# esp32_hr_module.net
KiCad netlist of a schematic drawn in EAGLE
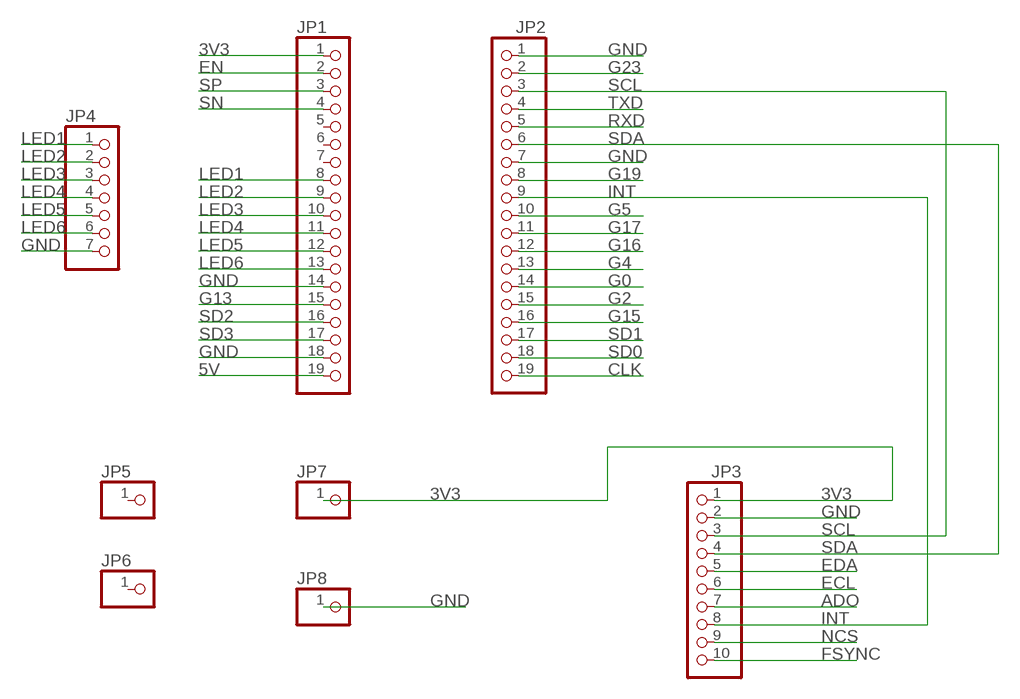
[diagram p0: schematic, sheet 1]

(export (version "E")
  (design (tool "Eeschema 10.0.6"))
  (components
    (comp (ref "JP1")
      (value "PINHD-1X19")
      (footprint "eagle-import:1X19")
      (libsource (lib "eagle-import") (part "PINHD-1X19"))
    )
    (comp (ref "JP2")
      (value "PINHD-1X19")
      (footprint "eagle-import:1X19")
      (libsource (lib "eagle-import") (part "PINHD-1X19"))
    )
    (comp (ref "JP3")
      (value "PINHD-1X10")
      (footprint "eagle-import:1X10")
      (libsource (lib "eagle-import") (part "PINHD-1X10"))
    )
    (comp (ref "JP4")
      (value "PINHD-1X7")
      (footprint "eagle-import:1X07")
      (libsource (lib "eagle-import") (part "PINHD-1X7"))
    )
    (comp (ref "JP5")
      (value "PINHD-1X1")
      (footprint "eagle-import:1X01")
      (libsource (lib "eagle-import") (part "PINHD-1X1"))
    )
    (comp (ref "JP6")
      (value "PINHD-1X1")
      (footprint "eagle-import:1X01")
      (libsource (lib "eagle-import") (part "PINHD-1X1"))
    )
    (comp (ref "JP7")
      (value "PINHD-1X1")
      (footprint "eagle-import:1X01")
      (libsource (lib "eagle-import") (part "PINHD-1X1"))
    )
    (comp (ref "JP8")
      (value "PINHD-1X1")
      (footprint "eagle-import:1X01")
      (libsource (lib "eagle-import") (part "PINHD-1X1"))
    )
  )
  (nets
    (net (code "1") (name "/3V3") (class "Default")
      (node (ref "JP1") (pin "1") (pinfunction "1_1") (pintype "passive"))
      (node (ref "JP3") (pin "1") (pinfunction "1_1") (pintype "passive"))
      (node (ref "JP7") (pin "1") (pinfunction "1_1") (pintype "passive"))
    )
    (net (code "2") (name "/5V") (class "Default")
      (node (ref "JP1") (pin "19") (pinfunction "19_19") (pintype "passive"))
    )
    (net (code "3") (name "/ADO") (class "Default")
      (node (ref "JP3") (pin "7") (pinfunction "7_7") (pintype "passive"))
    )
    (net (code "4") (name "/CLK") (class "Default")
      (node (ref "JP2") (pin "19") (pinfunction "19_19") (pintype "passive"))
    )
    (net (code "5") (name "/ECL") (class "Default")
      (node (ref "JP3") (pin "6") (pinfunction "6_6") (pintype "passive"))
    )
    (net (code "6") (name "/EDA") (class "Default")
      (node (ref "JP3") (pin "5") (pinfunction "5_5") (pintype "passive"))
    )
    (net (code "7") (name "/EN") (class "Default")
      (node (ref "JP1") (pin "2") (pinfunction "2_2") (pintype "passive"))
    )
    (net (code "8") (name "/FSYNC") (class "Default")
      (node (ref "JP3") (pin "10") (pinfunction "10_10") (pintype "passive"))
    )
    (net (code "9") (name "/G0") (class "Default")
      (node (ref "JP2") (pin "14") (pinfunction "14_14") (pintype "passive"))
    )
    (net (code "10") (name "/G2") (class "Default")
      (node (ref "JP2") (pin "15") (pinfunction "15_15") (pintype "passive"))
    )
    (net (code "11") (name "/G4") (class "Default")
      (node (ref "JP2") (pin "13") (pinfunction "13_13") (pintype "passive"))
    )
    (net (code "12") (name "/G5") (class "Default")
      (node (ref "JP2") (pin "10") (pinfunction "10_10") (pintype "passive"))
    )
    (net (code "13") (name "/G13") (class "Default")
      (node (ref "JP1") (pin "15") (pinfunction "15_15") (pintype "passive"))
    )
    (net (code "14") (name "/G15") (class "Default")
      (node (ref "JP2") (pin "16") (pinfunction "16_16") (pintype "passive"))
    )
    (net (code "15") (name "/G16") (class "Default")
      (node (ref "JP2") (pin "12") (pinfunction "12_12") (pintype "passive"))
    )
    (net (code "16") (name "/G17") (class "Default")
      (node (ref "JP2") (pin "11") (pinfunction "11_11") (pintype "passive"))
    )
    (net (code "17") (name "/G19") (class "Default")
      (node (ref "JP2") (pin "8") (pinfunction "8_8") (pintype "passive"))
    )
    (net (code "18") (name "/G23") (class "Default")
      (node (ref "JP2") (pin "2") (pinfunction "2_2") (pintype "passive"))
    )
    (net (code "19") (name "/GND") (class "Default")
      (node (ref "JP1") (pin "14") (pinfunction "14_14") (pintype "passive"))
      (node (ref "JP1") (pin "18") (pinfunction "18_18") (pintype "passive"))
      (node (ref "JP2") (pin "1") (pinfunction "1_1") (pintype "passive"))
      (node (ref "JP2") (pin "7") (pinfunction "7_7") (pintype "passive"))
      (node (ref "JP3") (pin "2") (pinfunction "2_2") (pintype "passive"))
      (node (ref "JP4") (pin "7") (pinfunction "7_7") (pintype "passive"))
      (node (ref "JP8") (pin "1") (pinfunction "1_1") (pintype "passive"))
    )
    (net (code "20") (name "/INT") (class "Default")
      (node (ref "JP2") (pin "9") (pinfunction "9_9") (pintype "passive"))
      (node (ref "JP3") (pin "8") (pinfunction "8_8") (pintype "passive"))
    )
    (net (code "21") (name "/LED1") (class "Default")
      (node (ref "JP1") (pin "8") (pinfunction "8_8") (pintype "passive"))
      (node (ref "JP4") (pin "1") (pinfunction "1_1") (pintype "passive"))
    )
    (net (code "22") (name "/LED2") (class "Default")
      (node (ref "JP1") (pin "9") (pinfunction "9_9") (pintype "passive"))
      (node (ref "JP4") (pin "2") (pinfunction "2_2") (pintype "passive"))
    )
    (net (code "23") (name "/LED3") (class "Default")
      (node (ref "JP1") (pin "10") (pinfunction "10_10") (pintype "passive"))
      (node (ref "JP4") (pin "3") (pinfunction "3_3") (pintype "passive"))
    )
    (net (code "24") (name "/LED4") (class "Default")
      (node (ref "JP1") (pin "11") (pinfunction "11_11") (pintype "passive"))
      (node (ref "JP4") (pin "4") (pinfunction "4_4") (pintype "passive"))
    )
    (net (code "25") (name "/LED5") (class "Default")
      (node (ref "JP1") (pin "12") (pinfunction "12_12") (pintype "passive"))
      (node (ref "JP4") (pin "5") (pinfunction "5_5") (pintype "passive"))
    )
    (net (code "26") (name "/LED6") (class "Default")
      (node (ref "JP1") (pin "13") (pinfunction "13_13") (pintype "passive"))
      (node (ref "JP4") (pin "6") (pinfunction "6_6") (pintype "passive"))
    )
    (net (code "27") (name "/NCS") (class "Default")
      (node (ref "JP3") (pin "9") (pinfunction "9_9") (pintype "passive"))
    )
    (net (code "28") (name "/RXD") (class "Default")
      (node (ref "JP2") (pin "5") (pinfunction "5_5") (pintype "passive"))
    )
    (net (code "29") (name "/SCL") (class "Default")
      (node (ref "JP2") (pin "3") (pinfunction "3_3") (pintype "passive"))
      (node (ref "JP3") (pin "3") (pinfunction "3_3") (pintype "passive"))
    )
    (net (code "30") (name "/SD0") (class "Default")
      (node (ref "JP2") (pin "18") (pinfunction "18_18") (pintype "passive"))
    )
    (net (code "31") (name "/SD1") (class "Default")
      (node (ref "JP2") (pin "17") (pinfunction "17_17") (pintype "passive"))
    )
    (net (code "32") (name "/SD2") (class "Default")
      (node (ref "JP1") (pin "16") (pinfunction "16_16") (pintype "passive"))
    )
    (net (code "33") (name "/SD3") (class "Default")
      (node (ref "JP1") (pin "17") (pinfunction "17_17") (pintype "passive"))
    )
    (net (code "34") (name "/SDA") (class "Default")
      (node (ref "JP2") (pin "6") (pinfunction "6_6") (pintype "passive"))
      (node (ref "JP3") (pin "4") (pinfunction "4_4") (pintype "passive"))
    )
    (net (code "35") (name "/SN") (class "Default")
      (node (ref "JP1") (pin "4") (pinfunction "4_4") (pintype "passive"))
    )
    (net (code "36") (name "/SP") (class "Default")
      (node (ref "JP1") (pin "3") (pinfunction "3_3") (pintype "passive"))
    )
    (net (code "37") (name "/TXD") (class "Default")
      (node (ref "JP2") (pin "4") (pinfunction "4_4") (pintype "passive"))
    )
    (net (code "38") (name "unconnected-(JP1-Pad5)") (class "Default")
      (node (ref "JP1") (pin "5") (pinfunction "5_5") (pintype "passive"))
    )
    (net (code "39") (name "unconnected-(JP1-Pad6)") (class "Default")
      (node (ref "JP1") (pin "6") (pinfunction "6_6") (pintype "passive"))
    )
    (net (code "40") (name "unconnected-(JP1-Pad7)") (class "Default")
      (node (ref "JP1") (pin "7") (pinfunction "7_7") (pintype "passive"))
    )
    (net (code "41") (name "unconnected-(JP5-Pad1)") (class "Default")
      (node (ref "JP5") (pin "1") (pinfunction "1_1") (pintype "passive"))
    )
    (net (code "42") (name "unconnected-(JP6-Pad1)") (class "Default")
      (node (ref "JP6") (pin "1") (pinfunction "1_1") (pintype "passive"))
    )
  )
)
